# Regulators_and_Buck_Converters.net
KiCad netlist of a schematic drawn in Altium Designer
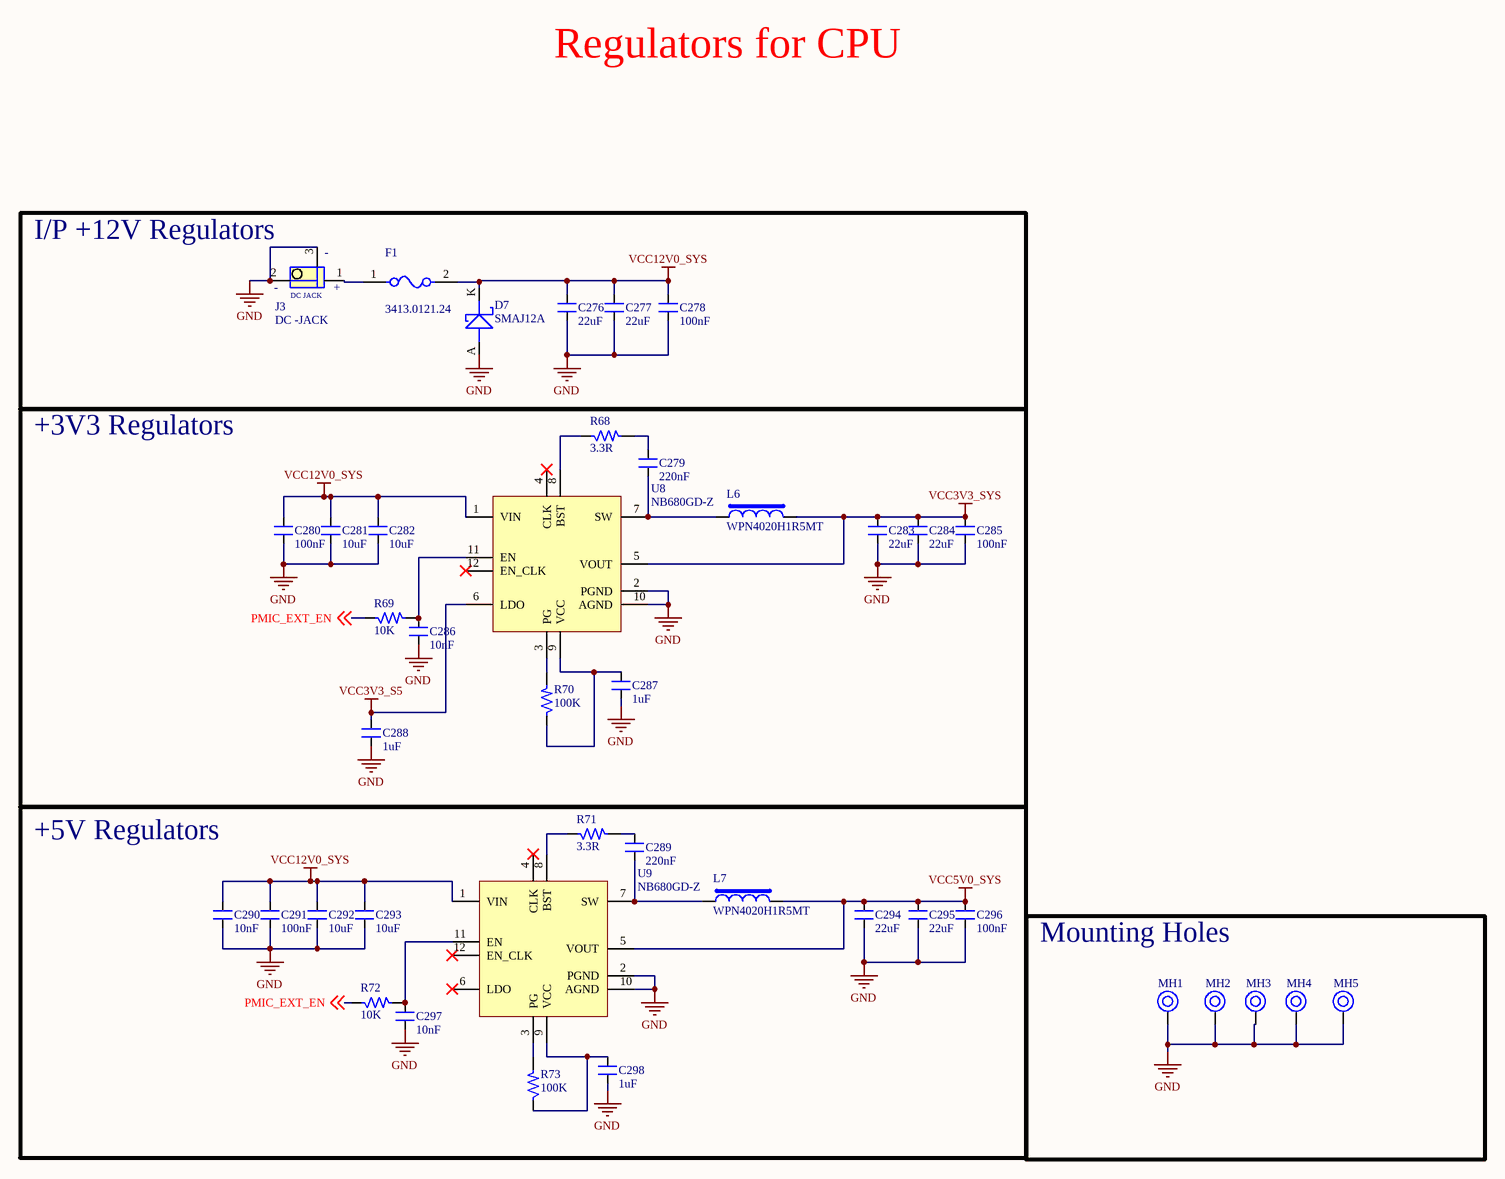
[diagram p0: Regulators and Buck Converters.SchDoc]

(export (version "E")
  (design (tool "Eeschema 10.0.6"))
  (components
    (comp (ref "C276")
      (value "22uF")
      (footprint "CAP_0805")
      (description "22µF ±20% 25V Ceramic Capacitor X5R 0805 (2012 Metric)")
      (fields
        (field (name "MANUFACTURER") "Murata Electronics")
        (field (name "MANUFACTURER PART NUMBER") "GRM21BR61E226ME44K")
      )
      (libsource (lib "RK3399 _Module_Schlib") (part "CAP_22uF-25V-20%-0805"))
    )
    (comp (ref "C277")
      (value "22uF")
      (footprint "CAP_0805")
      (description "22µF ±20% 25V Ceramic Capacitor X5R 0805 (2012 Metric)")
      (fields
        (field (name "MANUFACTURER") "Murata Electronics")
        (field (name "MANUFACTURER PART NUMBER") "GRM21BR61E226ME44K")
      )
      (libsource (lib "RK3399 _Module_Schlib") (part "CAP_22uF-25V-20%-0805"))
    )
    (comp (ref "C278")
      (value "100nF")
      (footprint "CAP_0805")
      (description "0.1µF ±10% 25V Ceramic Capacitor X7R 0805 (2012 Metric)")
      (fields
        (field (name "MANUFACTURER") "Yageo")
        (field (name "MANUFACTURER PART NUMBER") "CC0805KRX7R8BB104")
      )
      (libsource (lib "RK3399 _Module_Schlib") (part "CAP_100nF-25V-10%-0805"))
    )
    (comp (ref "C279")
      (value "220nF")
      (footprint "CAP_0603")
      (description "0.22µF ±10% 10V Ceramic Capacitor X7R 0603 (1608 Metric)")
      (fields
        (field (name "MANUFACTURER") "Yageo")
        (field (name "MANUFACTURER PART NUMBER") "CC0603KRX7R6BB224")
      )
      (libsource (lib "RK3399 _Module_Schlib") (part "CAP_220nF-10V-10%-0603"))
    )
    (comp (ref "C280")
      (value "100nF")
      (footprint "CAP_0805")
      (description "0.1µF ±10% 25V Ceramic Capacitor X7R 0805 (2012 Metric)")
      (fields
        (field (name "MANUFACTURER") "Yageo")
        (field (name "MANUFACTURER PART NUMBER") "CC0805KRX7R8BB104")
      )
      (libsource (lib "RK3399 _Module_Schlib") (part "CAP_100nF-25V-10%-0805"))
    )
    (comp (ref "C281")
      (value "10uF")
      (footprint "CAP_0805")
      (description "10µF ±10% 25V Ceramic Capacitor X5R 0805 (2012 Metric)")
      (fields
        (field (name "MANUFACTURER") "Murata Electronics")
        (field (name "MANUFACTURER PART NUMBER") "GRM21BR61E106KA73K")
      )
      (libsource (lib "RK3399 _Module_Schlib") (part "CAP_10uF-25V-10%-0805"))
    )
    (comp (ref "C282")
      (value "10uF")
      (footprint "CAP_0805")
      (description "10µF ±10% 25V Ceramic Capacitor X5R 0805 (2012 Metric)")
      (fields
        (field (name "MANUFACTURER") "Murata Electronics")
        (field (name "MANUFACTURER PART NUMBER") "GRM21BR61E106KA73K")
      )
      (libsource (lib "RK3399 _Module_Schlib") (part "CAP_10uF-25V-10%-0805"))
    )
    (comp (ref "C283")
      (value "22uF")
      (footprint "CAP_0805")
      (description "22µF ±20% 25V Ceramic Capacitor X5R 0805 (2012 Metric)")
      (fields
        (field (name "MANUFACTURER") "Murata Electronics")
        (field (name "MANUFACTURER PART NUMBER") "GRM21BR61E226ME44K")
      )
      (libsource (lib "RK3399 _Module_Schlib") (part "CAP_22uF-25V-20%-0805"))
    )
    (comp (ref "C284")
      (value "22uF")
      (footprint "CAP_0805")
      (description "22µF ±20% 25V Ceramic Capacitor X5R 0805 (2012 Metric)")
      (fields
        (field (name "MANUFACTURER") "Murata Electronics")
        (field (name "MANUFACTURER PART NUMBER") "GRM21BR61E226ME44K")
      )
      (libsource (lib "RK3399 _Module_Schlib") (part "CAP_22uF-25V-20%-0805"))
    )
    (comp (ref "C285")
      (value "100nF")
      (footprint "CAP_0603")
      (description "0.1µF ±10% 10V Ceramic Capacitor X7R 0603 (1608 Metric)")
      (fields
        (field (name "MANUFACTURER") "Yageo")
        (field (name "MANUFACTURER PART NUMBER") "CC0603KRX7R6BB104")
      )
      (libsource (lib "RK3399 _Module_Schlib") (part "CAP_100nF-10V-5%-0603"))
    )
    (comp (ref "C286")
      (value "10nF")
      (footprint "CAP_0603")
      (description "10000pF ±10% 10V Ceramic Capacitor X7R 0603 (1608 Metric)")
      (fields
        (field (name "MANUFACTURER") "KEMET")
        (field (name "MANUFACTURER PART NUMBER") "C0603C103K8RACTU")
      )
      (libsource (lib "RK3399 _Module_Schlib") (part "CAP_10nF-10V-10%-0603"))
    )
    (comp (ref "C287")
      (value "1uF")
      (footprint "CAP_0603")
      (description "1µF ±10% 10V Ceramic Capacitor X5R 0603 (1608 Metric)")
      (fields
        (field (name "MANUFACTURER") "Samsung Electro-Mechanics")
        (field (name "MANUFACTURER PART NUMBER") "CL10A105KP8NNNC")
      )
      (libsource (lib "RK3399 _Module_Schlib") (part "CAP_1uF-10V-5%-0603"))
    )
    (comp (ref "C288")
      (value "1uF")
      (footprint "CAP_0603")
      (description "1µF ±10% 10V Ceramic Capacitor X5R 0603 (1608 Metric)")
      (fields
        (field (name "MANUFACTURER") "Samsung Electro-Mechanics")
        (field (name "MANUFACTURER PART NUMBER") "CL10A105KP8NNNC")
      )
      (libsource (lib "RK3399 _Module_Schlib") (part "CAP_1uF-10V-5%-0603"))
    )
    (comp (ref "C289")
      (value "220nF")
      (footprint "CAP_0603")
      (description "0.22µF ±10% 10V Ceramic Capacitor X7R 0603 (1608 Metric)")
      (fields
        (field (name "MANUFACTURER") "Yageo")
        (field (name "MANUFACTURER PART NUMBER") "CC0603KRX7R6BB224")
      )
      (libsource (lib "RK3399 _Module_Schlib") (part "CAP_220nF-10V-10%-0603"))
    )
    (comp (ref "C290")
      (value "10nF")
      (footprint "CAP_0603")
      (description "10000pF ±10% 10V Ceramic Capacitor X7R 0603 (1608 Metric)")
      (fields
        (field (name "MANUFACTURER") "KEMET")
        (field (name "MANUFACTURER PART NUMBER") "C0603C103K8RACTU")
      )
      (libsource (lib "RK3399 _Module_Schlib") (part "CAP_10nF-10V-10%-0603"))
    )
    (comp (ref "C291")
      (value "100nF")
      (footprint "CAP_0805")
      (description "0.1µF ±10% 25V Ceramic Capacitor X7R 0805 (2012 Metric)")
      (fields
        (field (name "MANUFACTURER") "Yageo")
        (field (name "MANUFACTURER PART NUMBER") "CC0805KRX7R8BB104")
      )
      (libsource (lib "RK3399 _Module_Schlib") (part "CAP_100nF-25V-10%-0805"))
    )
    (comp (ref "C292")
      (value "10uF")
      (footprint "CAP_0805")
      (description "10µF ±10% 25V Ceramic Capacitor X5R 0805 (2012 Metric)")
      (fields
        (field (name "MANUFACTURER") "Murata Electronics")
        (field (name "MANUFACTURER PART NUMBER") "GRM21BR61E106KA73K")
      )
      (libsource (lib "RK3399 _Module_Schlib") (part "CAP_10uF-25V-10%-0805"))
    )
    (comp (ref "C293")
      (value "10uF")
      (footprint "CAP_0805")
      (description "10µF ±10% 25V Ceramic Capacitor X5R 0805 (2012 Metric)")
      (fields
        (field (name "MANUFACTURER") "Murata Electronics")
        (field (name "MANUFACTURER PART NUMBER") "GRM21BR61E106KA73K")
      )
      (libsource (lib "RK3399 _Module_Schlib") (part "CAP_10uF-25V-10%-0805"))
    )
    (comp (ref "C294")
      (value "22uF")
      (footprint "CAP_0805")
      (description "22µF ±20% 25V Ceramic Capacitor X5R 0805 (2012 Metric)")
      (fields
        (field (name "MANUFACTURER") "Murata Electronics")
        (field (name "MANUFACTURER PART NUMBER") "GRM21BR61E226ME44K")
      )
      (libsource (lib "RK3399 _Module_Schlib") (part "CAP_22uF-25V-20%-0805"))
    )
    (comp (ref "C295")
      (value "22uF")
      (footprint "CAP_0805")
      (description "22µF ±20% 25V Ceramic Capacitor X5R 0805 (2012 Metric)")
      (fields
        (field (name "MANUFACTURER") "Murata Electronics")
        (field (name "MANUFACTURER PART NUMBER") "GRM21BR61E226ME44K")
      )
      (libsource (lib "RK3399 _Module_Schlib") (part "CAP_22uF-25V-20%-0805"))
    )
    (comp (ref "C296")
      (value "100nF")
      (footprint "CAP_0603")
      (description "0.1µF ±10% 10V Ceramic Capacitor X7R 0603 (1608 Metric)")
      (fields
        (field (name "MANUFACTURER") "Yageo")
        (field (name "MANUFACTURER PART NUMBER") "CC0603KRX7R6BB104")
      )
      (libsource (lib "RK3399 _Module_Schlib") (part "CAP_100nF-10V-5%-0603"))
    )
    (comp (ref "C297")
      (value "10nF")
      (footprint "CAP_0603")
      (description "10000pF ±10% 10V Ceramic Capacitor X7R 0603 (1608 Metric)")
      (fields
        (field (name "MANUFACTURER") "KEMET")
        (field (name "MANUFACTURER PART NUMBER") "C0603C103K8RACTU")
      )
      (libsource (lib "RK3399 _Module_Schlib") (part "CAP_10nF-10V-10%-0603"))
    )
    (comp (ref "C298")
      (value "1uF")
      (footprint "CAP_0603")
      (description "1µF ±10% 10V Ceramic Capacitor X5R 0603 (1608 Metric)")
      (fields
        (field (name "MANUFACTURER") "Samsung Electro-Mechanics")
        (field (name "MANUFACTURER PART NUMBER") "CL10A105KP8NNNC")
      )
      (libsource (lib "RK3399 _Module_Schlib") (part "CAP_1uF-10V-5%-0603"))
    )
    (comp (ref "D7")
      (value "SMAJ12A")
      (footprint "DIO_SMA_DO-214AC")
      (description "19.9V Clamp 20.1A Ipp Tvs Diode Surface Mount DO-214AC (SMA)")
      (fields (field (name "MANUFACTURER") "Littelfuse Inc."))
      (libsource (lib "RK3399 _Module_Schlib") (part "DIO-T_13.3V-19.9V-20.1A-DO-214AC"))
    )
    (comp (ref "F1")
      (value "3413.0121.24")
      (footprint "RES_1206")
      (description "3A 32V AC 63V DC Fuse Board Mount (Cartridge Style Excluded) Surface Mount 1206 (3216 Metric)")
      (fields (field (name "MANUFACTURER") "Schurter Inc."))
      (libsource (lib "RK3399 _Module_Schlib") (part "FUSE_3A-32V-1206"))
    )
    (comp (ref "J3")
      (value "DC -JACK")
      (footprint "CON3_129_PJ-002A_TH_RA")
      (description "3 Pins, 1 Row 228mil Pitch, right angle Connector, male")
      (fields (field (name "MANUFACTURER") "JST") (field (name "MANUFACTURER PART NUMBER") "PJ-002A"))
      (libsource (lib "RK3399 _Module_Schlib") (part "CON-PLG_3X1-228-DC_JACK"))
    )
    (comp (ref "L6")
      (value "WPN4020H1R5MT")
      (footprint "IND_1616")
      (fields (field (name "MANUFACTURER") "Sunlord"))
      (libsource (lib "RK3399 _Module_Schlib") (part "IND_1.5uH-6A-20%-SMD"))
    )
    (comp (ref "L7")
      (value "WPN4020H1R5MT")
      (footprint "IND_1616")
      (fields (field (name "MANUFACTURER") "Sunlord"))
      (libsource (lib "RK3399 _Module_Schlib") (part "IND_1.5uH-6A-20%-SMD"))
    )
    (comp (ref "MH1")
      (value "Mounting Hole")
      (footprint "MOUNTING")
      (fields (field (name "MANUFACTURER PART NUMBER") "NA"))
      (libsource (lib "EsteemPCB_COB_Course_intlib") (part "MH_3.5H_6D"))
    )
    (comp (ref "MH2")
      (value "Mounting Hole")
      (footprint "MOUNTING")
      (fields (field (name "MANUFACTURER PART NUMBER") "NA"))
      (libsource (lib "EsteemPCB_COB_Course_intlib") (part "MH_3.5H_6D"))
    )
    (comp (ref "MH3")
      (value "Mounting Hole")
      (footprint "MOUNTING")
      (fields (field (name "MANUFACTURER PART NUMBER") "NA"))
      (libsource (lib "EsteemPCB_COB_Course_intlib") (part "MH_3.5H_6D"))
    )
    (comp (ref "MH4")
      (value "Mounting Hole")
      (footprint "MOUNTING")
      (fields (field (name "MANUFACTURER PART NUMBER") "NA"))
      (libsource (lib "EsteemPCB_COB_Course_intlib") (part "MH_3.5H_6D"))
    )
    (comp (ref "MH5")
      (value "Mounting Hole")
      (footprint "MOUNTING")
      (fields (field (name "MANUFACTURER PART NUMBER") "NA"))
      (libsource (lib "EsteemPCB_COB_Course_intlib") (part "MH_3.5H_6D"))
    )
    (comp (ref "R68")
      (value "3.3R")
      (footprint "RES_0603")
      (fields
        (field (name "MANUFACTURER") "Panasonic Electronic Components")
        (field (name "MANUFACTURER PART NUMBER") "ERJ-3RQF3R3V")
      )
      (libsource (lib "RK3399 _Module_Schlib") (part "RES_3.3R-0.1W-1%-0603"))
    )
    (comp (ref "R69")
      (value "10K")
      (footprint "RES_0603")
      (description "10 kOhms ±1% 0.1W, 1/10W Chip Resistor 0603 (1608 Metric) Thick Film")
      (fields
        (field (name "MANUFACTURER") "Yageo")
        (field (name "MANUFACTURER PART NUMBER") "RC0603FR-0710KL")
      )
      (libsource (lib "RK3399 _Module_Schlib") (part "RES_10K-0.1W-1%-0603"))
    )
    (comp (ref "R70")
      (value "100K")
      (footprint "RES_0603")
      (description "100 kOhms ±1% 0.1W, 1/10W Chip Resistor 0603 (1608 Metric) Automotive AEC-Q200 Thick Film")
      (fields
        (field (name "MANUFACTURER") "tackpole Electronics Inc")
        (field (name "MANUFACTURER PART NUMBER") "RMCF0603FT100K")
      )
      (libsource (lib "RK3399 _Module_Schlib") (part "RES_100K-0.1W-1%-0603"))
    )
    (comp (ref "R71")
      (value "3.3R")
      (footprint "RES_0603")
      (fields
        (field (name "MANUFACTURER") "Panasonic Electronic Components")
        (field (name "MANUFACTURER PART NUMBER") "ERJ-3RQF3R3V")
      )
      (libsource (lib "RK3399 _Module_Schlib") (part "RES_3.3R-0.1W-1%-0603"))
    )
    (comp (ref "R72")
      (value "10K")
      (footprint "RES_0603")
      (description "10 kOhms ±1% 0.1W, 1/10W Chip Resistor 0603 (1608 Metric) Thick Film")
      (fields
        (field (name "MANUFACTURER") "Yageo")
        (field (name "MANUFACTURER PART NUMBER") "RC0603FR-0710KL")
      )
      (libsource (lib "RK3399 _Module_Schlib") (part "RES_10K-0.1W-1%-0603"))
    )
    (comp (ref "R73")
      (value "100K")
      (footprint "RES_0603")
      (description "100 kOhms ±1% 0.1W, 1/10W Chip Resistor 0603 (1608 Metric) Automotive AEC-Q200 Thick Film")
      (fields
        (field (name "MANUFACTURER") "tackpole Electronics Inc")
        (field (name "MANUFACTURER PART NUMBER") "RMCF0603FT100K")
      )
      (libsource (lib "RK3399 _Module_Schlib") (part "RES_100K-0.1W-1%-0603"))
    )
    (comp (ref "U8")
      (value "NB680GD-Z")
      (footprint "QFN-12_19_118X118_SMD")
      (description "Switching Voltage Regulators 26V Fixed 3.3 V-8A Sync Buck Converter")
      (fields (field (name "MANUFACTURER") "Monolithic Power Systems (MPS)"))
      (libsource (lib "RK3399 _Module_Schlib") (part "REG_3.3V-26V-8A-QFN-12"))
    )
    (comp (ref "U9")
      (value "NB680GD-Z")
      (footprint "QFN-12_19_118X118_SMD")
      (description "Switching Voltage Regulators 26V Fixed 3.3 V-8A Sync Buck Converter")
      (fields (field (name "MANUFACTURER") "Monolithic Power Systems (MPS)"))
      (libsource (lib "RK3399 _Module_Schlib") (part "REG_3.3V-26V-8A-QFN-12"))
    )
  )
  (nets
    (net (code "1") (name "GND") (class "Default")
      (node (ref "C276") (pin "1") (pinfunction "1_1") (pintype "passive"))
      (node (ref "C277") (pin "1") (pinfunction "1_1") (pintype "passive"))
      (node (ref "C278") (pin "1") (pinfunction "1_1") (pintype "passive"))
      (node (ref "C280") (pin "1") (pinfunction "1_1") (pintype "passive"))
      (node (ref "C281") (pin "1") (pinfunction "1_1") (pintype "passive"))
      (node (ref "C282") (pin "1") (pinfunction "1_1") (pintype "passive"))
      (node (ref "C283") (pin "1") (pinfunction "1_1") (pintype "passive"))
      (node (ref "C284") (pin "1") (pinfunction "1_1") (pintype "passive"))
      (node (ref "C285") (pin "1") (pinfunction "1_1") (pintype "passive"))
      (node (ref "C286") (pin "1") (pinfunction "1_1") (pintype "passive"))
      (node (ref "C287") (pin "1") (pinfunction "1_1") (pintype "passive"))
      (node (ref "C288") (pin "1") (pinfunction "1_1") (pintype "passive"))
      (node (ref "C290") (pin "1") (pinfunction "1_1") (pintype "passive"))
      (node (ref "C291") (pin "1") (pinfunction "1_1") (pintype "passive"))
      (node (ref "C292") (pin "1") (pinfunction "1_1") (pintype "passive"))
      (node (ref "C293") (pin "1") (pinfunction "1_1") (pintype "passive"))
      (node (ref "C294") (pin "1") (pinfunction "1_1") (pintype "passive"))
      (node (ref "C295") (pin "1") (pinfunction "1_1") (pintype "passive"))
      (node (ref "C296") (pin "1") (pinfunction "1_1") (pintype "passive"))
      (node (ref "C297") (pin "1") (pinfunction "1_1") (pintype "passive"))
      (node (ref "C298") (pin "1") (pinfunction "1_1") (pintype "passive"))
      (node (ref "D7") (pin "A") (pinfunction "A_A") (pintype "passive"))
      (node (ref "J3") (pin "2") (pinfunction "2_2") (pintype "passive"))
      (node (ref "J3") (pin "3") (pinfunction "-_3") (pintype "passive"))
      (node (ref "MH1") (pin "1") (pinfunction "1_1") (pintype "passive"))
      (node (ref "MH2") (pin "1") (pinfunction "1_1") (pintype "passive"))
      (node (ref "MH3") (pin "1") (pinfunction "1_1") (pintype "passive"))
      (node (ref "MH4") (pin "1") (pinfunction "1_1") (pintype "passive"))
      (node (ref "MH5") (pin "1") (pinfunction "1_1") (pintype "passive"))
      (node (ref "U8") (pin "10") (pinfunction "AGND_10") (pintype "passive"))
      (node (ref "U8") (pin "2") (pinfunction "PGND_2") (pintype "passive"))
      (node (ref "U9") (pin "10") (pinfunction "AGND_10") (pintype "passive"))
      (node (ref "U9") (pin "2") (pinfunction "PGND_2") (pintype "passive"))
    )
    (net (code "2") (name "Net-(C279-Pad2)") (class "Default")
      (node (ref "C279") (pin "2") (pinfunction "2_2") (pintype "passive"))
      (node (ref "R68") (pin "2") (pinfunction "2_2") (pintype "passive"))
    )
    (net (code "3") (name "Net-(C289-Pad2)") (class "Default")
      (node (ref "C289") (pin "2") (pinfunction "2_2") (pintype "passive"))
      (node (ref "R71") (pin "2") (pinfunction "2_2") (pintype "passive"))
    )
    (net (code "4") (name "Net-(F1-Pad1)") (class "Default")
      (node (ref "F1") (pin "1") (pinfunction "1_1") (pintype "passive"))
      (node (ref "J3") (pin "1") (pinfunction "1_1") (pintype "passive"))
    )
    (net (code "5") (name "Net-(U8-BST)") (class "Default")
      (node (ref "R68") (pin "1") (pinfunction "1_1") (pintype "passive"))
      (node (ref "U8") (pin "8") (pinfunction "BST_8") (pintype "passive"))
    )
    (net (code "6") (name "Net-(U8-EN)") (class "Default")
      (node (ref "C286") (pin "2") (pinfunction "2_2") (pintype "passive"))
      (node (ref "R69") (pin "2") (pinfunction "2_2") (pintype "passive"))
      (node (ref "U8") (pin "11") (pinfunction "EN_11") (pintype "passive"))
    )
    (net (code "7") (name "Net-(U8-PG)") (class "Default")
      (node (ref "R70") (pin "2") (pinfunction "2_2") (pintype "passive"))
      (node (ref "U8") (pin "3") (pinfunction "PG_3") (pintype "passive"))
    )
    (net (code "8") (name "Net-(U8-SW)") (class "Default")
      (node (ref "C279") (pin "1") (pinfunction "1_1") (pintype "passive"))
      (node (ref "L6") (pin "1") (pinfunction "1_1") (pintype "passive"))
      (node (ref "U8") (pin "7") (pinfunction "SW_7") (pintype "passive"))
    )
    (net (code "9") (name "Net-(U8-VCC)") (class "Default")
      (node (ref "C287") (pin "2") (pinfunction "2_2") (pintype "passive"))
      (node (ref "R70") (pin "1") (pinfunction "1_1") (pintype "passive"))
      (node (ref "U8") (pin "9") (pinfunction "VCC_9") (pintype "passive"))
    )
    (net (code "10") (name "Net-(U9-BST)") (class "Default")
      (node (ref "R71") (pin "1") (pinfunction "1_1") (pintype "passive"))
      (node (ref "U9") (pin "8") (pinfunction "BST_8") (pintype "passive"))
    )
    (net (code "11") (name "Net-(U9-EN)") (class "Default")
      (node (ref "C297") (pin "2") (pinfunction "2_2") (pintype "passive"))
      (node (ref "R72") (pin "2") (pinfunction "2_2") (pintype "passive"))
      (node (ref "U9") (pin "11") (pinfunction "EN_11") (pintype "passive"))
    )
    (net (code "12") (name "Net-(U9-PG)") (class "Default")
      (node (ref "R73") (pin "2") (pinfunction "2_2") (pintype "passive"))
      (node (ref "U9") (pin "3") (pinfunction "PG_3") (pintype "passive"))
    )
    (net (code "13") (name "Net-(U9-SW)") (class "Default")
      (node (ref "C289") (pin "1") (pinfunction "1_1") (pintype "passive"))
      (node (ref "L7") (pin "1") (pinfunction "1_1") (pintype "passive"))
      (node (ref "U9") (pin "7") (pinfunction "SW_7") (pintype "passive"))
    )
    (net (code "14") (name "Net-(U9-VCC)") (class "Default")
      (node (ref "C298") (pin "2") (pinfunction "2_2") (pintype "passive"))
      (node (ref "R73") (pin "1") (pinfunction "1_1") (pintype "passive"))
      (node (ref "U9") (pin "9") (pinfunction "VCC_9") (pintype "passive"))
    )
    (net (code "15") (name "PMIC_EXT_EN") (class "Default")
      (node (ref "R69") (pin "1") (pinfunction "1_1") (pintype "passive"))
      (node (ref "R72") (pin "1") (pinfunction "1_1") (pintype "passive"))
    )
    (net (code "16") (name "VCC3V3_S5") (class "Default")
      (node (ref "C288") (pin "2") (pinfunction "2_2") (pintype "passive"))
      (node (ref "U8") (pin "6") (pinfunction "LDO_6") (pintype "passive"))
    )
    (net (code "17") (name "VCC3V3_SYS") (class "Default")
      (node (ref "C283") (pin "2") (pinfunction "2_2") (pintype "passive"))
      (node (ref "C284") (pin "2") (pinfunction "2_2") (pintype "passive"))
      (node (ref "C285") (pin "2") (pinfunction "2_2") (pintype "passive"))
      (node (ref "L6") (pin "2") (pinfunction "2_2") (pintype "passive"))
      (node (ref "U8") (pin "5") (pinfunction "VOUT_5") (pintype "passive"))
    )
    (net (code "18") (name "VCC5V0_SYS") (class "Default")
      (node (ref "C294") (pin "2") (pinfunction "2_2") (pintype "passive"))
      (node (ref "C295") (pin "2") (pinfunction "2_2") (pintype "passive"))
      (node (ref "C296") (pin "2") (pinfunction "2_2") (pintype "passive"))
      (node (ref "L7") (pin "2") (pinfunction "2_2") (pintype "passive"))
      (node (ref "U9") (pin "5") (pinfunction "VOUT_5") (pintype "passive"))
    )
    (net (code "19") (name "VCC12V0_SYS") (class "Default")
      (node (ref "C276") (pin "2") (pinfunction "2_2") (pintype "passive"))
      (node (ref "C277") (pin "2") (pinfunction "2_2") (pintype "passive"))
      (node (ref "C278") (pin "2") (pinfunction "2_2") (pintype "passive"))
      (node (ref "C280") (pin "2") (pinfunction "2_2") (pintype "passive"))
      (node (ref "C281") (pin "2") (pinfunction "2_2") (pintype "passive"))
      (node (ref "C282") (pin "2") (pinfunction "2_2") (pintype "passive"))
      (node (ref "C290") (pin "2") (pinfunction "2_2") (pintype "passive"))
      (node (ref "C291") (pin "2") (pinfunction "2_2") (pintype "passive"))
      (node (ref "C292") (pin "2") (pinfunction "2_2") (pintype "passive"))
      (node (ref "C293") (pin "2") (pinfunction "2_2") (pintype "passive"))
      (node (ref "D7") (pin "K") (pinfunction "K_K") (pintype "passive"))
      (node (ref "F1") (pin "2") (pinfunction "2_2") (pintype "passive"))
      (node (ref "U8") (pin "1") (pinfunction "VIN_1") (pintype "passive"))
      (node (ref "U9") (pin "1") (pinfunction "VIN_1") (pintype "passive"))
    )
    (net (code "20") (name "unconnected-(U8-CLK-Pad4)") (class "Default")
      (node (ref "U8") (pin "4") (pinfunction "CLK_4") (pintype "passive+no_connect"))
    )
    (net (code "21") (name "unconnected-(U8-EN_CLK-Pad12)") (class "Default")
      (node (ref "U8") (pin "12") (pinfunction "EN_CLK_12") (pintype "passive+no_connect"))
    )
    (net (code "22") (name "unconnected-(U9-CLK-Pad4)") (class "Default")
      (node (ref "U9") (pin "4") (pinfunction "CLK_4") (pintype "passive+no_connect"))
    )
    (net (code "23") (name "unconnected-(U9-EN_CLK-Pad12)") (class "Default")
      (node (ref "U9") (pin "12") (pinfunction "EN_CLK_12") (pintype "passive+no_connect"))
    )
    (net (code "24") (name "unconnected-(U9-LDO-Pad6)") (class "Default")
      (node (ref "U9") (pin "6") (pinfunction "LDO_6") (pintype "passive+no_connect"))
    )
  )
)
